# ItsyBitsy_Qwiic.net
KiCad netlist of a schematic drawn in EAGLE
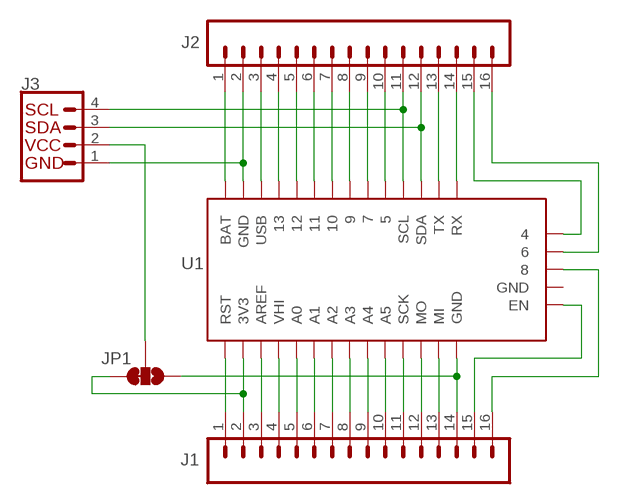
[diagram p0: schematic, sheet 1]

(export (version "E")
  (design (tool "Eeschema 10.0.6"))
  (components
    (comp (ref "J1")
      (value "CONN_161X16_NO_SILK")
      (footprint "eagle-import:1X16_NO_SILK")
      (libsource (lib "eagle-import") (part "CONN_161X16_NO_SILK"))
    )
    (comp (ref "J2")
      (value "CONN_161X16_NO_SILK")
      (footprint "eagle-import:1X16_NO_SILK")
      (libsource (lib "eagle-import") (part "CONN_161X16_NO_SILK"))
    )
    (comp (ref "J3")
      (value "QWIIC_CONNECTORJS-1MM")
      (footprint "eagle-import:1X04_1MM_RA")
      (libsource (lib "eagle-import") (part "QWIIC_CONNECTORJS-1MM"))
    )
    (comp (ref "JP1")
      (value "JUMPER-SMT_3_1-NC_TRACE_SILK")
      (footprint "eagle-import:SMT-JUMPER_3_1-NC_TRACE_SILK")
      (libsource (lib "eagle-import") (part "JUMPER-SMT_3_1-NC_TRACE_SILK"))
    )
    (comp (ref "U1")
      (value "ITSYBITSY-32U4-3V")
      (footprint "eagle-import:ITSYBITYS-32U4")
      (libsource (lib "eagle-import") (part "ITSYBITSY-32U4-3V"))
    )
  )
  (nets
    (net (code "1") (name "/GND") (class "Default")
      (node (ref "U1") (pin "P$16") (pinfunction "GND_P$16") (pintype "power_in"))
    )
    (net (code "2") (name "Net-(J1-Pad14)") (class "Default")
      (node (ref "J1") (pin "14") (pinfunction "14_14") (pintype "passive"))
      (node (ref "JP1") (pin "1") (pinfunction "1_1") (pintype "passive"))
      (node (ref "U1") (pin "P$14") (pinfunction "GND_P$14") (pintype "power_in"))
    )
    (net (code "3") (name "Net-(J3-GND)") (class "Default")
      (node (ref "J2") (pin "2") (pinfunction "2_2") (pintype "passive"))
      (node (ref "J3") (pin "1") (pinfunction "GND_1") (pintype "power_in"))
      (node (ref "U1") (pin "P$32") (pinfunction "GND_P$32") (pintype "power_in"))
    )
    (net (code "4") (name "Net-(J3-SCL)") (class "Default")
      (node (ref "J2") (pin "11") (pinfunction "11_11") (pintype "passive"))
      (node (ref "J3") (pin "4") (pinfunction "SCL_4") (pintype "passive"))
      (node (ref "U1") (pin "P$23") (pinfunction "SCL_P$23") (pintype "bidirectional"))
    )
    (net (code "5") (name "Net-(J3-SDA)") (class "Default")
      (node (ref "J2") (pin "12") (pinfunction "12_12") (pintype "passive"))
      (node (ref "J3") (pin "3") (pinfunction "SDA_3") (pintype "passive"))
      (node (ref "U1") (pin "P$22") (pinfunction "SDA_P$22") (pintype "bidirectional"))
    )
    (net (code "6") (name "Net-(J3-VCC)") (class "Default")
      (node (ref "J3") (pin "2") (pinfunction "VCC_2") (pintype "power_in"))
      (node (ref "JP1") (pin "2") (pinfunction "2_2") (pintype "passive"))
    )
    (net (code "7") (name "Net-(U1-3V3)") (class "Default")
      (node (ref "J1") (pin "2") (pinfunction "2_2") (pintype "passive"))
      (node (ref "JP1") (pin "3") (pinfunction "3_3") (pintype "passive"))
      (node (ref "U1") (pin "P$2") (pinfunction "3V3_P$2") (pintype "power_in"))
    )
    (net (code "8") (name "Net-(U1-4)") (class "Default")
      (node (ref "J2") (pin "15") (pinfunction "15_15") (pintype "passive"))
      (node (ref "U1") (pin "P$19") (pinfunction "4_P$19") (pintype "bidirectional"))
    )
    (net (code "9") (name "Net-(U1-5)") (class "Default")
      (node (ref "J2") (pin "10") (pinfunction "10_10") (pintype "passive"))
      (node (ref "U1") (pin "P$24") (pinfunction "5_P$24") (pintype "bidirectional"))
    )
    (net (code "10") (name "Net-(U1-6)") (class "Default")
      (node (ref "J2") (pin "16") (pinfunction "16_16") (pintype "passive"))
      (node (ref "U1") (pin "P$18") (pinfunction "6_P$18") (pintype "bidirectional"))
    )
    (net (code "11") (name "Net-(U1-7)") (class "Default")
      (node (ref "J2") (pin "9") (pinfunction "9_9") (pintype "passive"))
      (node (ref "U1") (pin "P$25") (pinfunction "7_P$25") (pintype "bidirectional"))
    )
    (net (code "12") (name "Net-(U1-8)") (class "Default")
      (node (ref "J1") (pin "16") (pinfunction "16_16") (pintype "passive"))
      (node (ref "U1") (pin "P$17") (pinfunction "8_P$17") (pintype "bidirectional"))
    )
    (net (code "13") (name "Net-(U1-9)") (class "Default")
      (node (ref "J2") (pin "8") (pinfunction "8_8") (pintype "passive"))
      (node (ref "U1") (pin "P$26") (pinfunction "9_P$26") (pintype "bidirectional"))
    )
    (net (code "14") (name "Net-(U1-10)") (class "Default")
      (node (ref "J2") (pin "7") (pinfunction "7_7") (pintype "passive"))
      (node (ref "U1") (pin "P$27") (pinfunction "10_P$27") (pintype "bidirectional"))
    )
    (net (code "15") (name "Net-(U1-11)") (class "Default")
      (node (ref "J2") (pin "6") (pinfunction "6_6") (pintype "passive"))
      (node (ref "U1") (pin "P$28") (pinfunction "11_P$28") (pintype "bidirectional"))
    )
    (net (code "16") (name "Net-(U1-12)") (class "Default")
      (node (ref "J2") (pin "5") (pinfunction "5_5") (pintype "passive"))
      (node (ref "U1") (pin "P$29") (pinfunction "12_P$29") (pintype "bidirectional"))
    )
    (net (code "17") (name "Net-(U1-13)") (class "Default")
      (node (ref "J2") (pin "4") (pinfunction "4_4") (pintype "passive"))
      (node (ref "U1") (pin "P$30") (pinfunction "13_P$30") (pintype "bidirectional"))
    )
    (net (code "18") (name "Net-(U1-A0)") (class "Default")
      (node (ref "J1") (pin "5") (pinfunction "5_5") (pintype "passive"))
      (node (ref "U1") (pin "P$5") (pinfunction "A0_P$5") (pintype "bidirectional"))
    )
    (net (code "19") (name "Net-(U1-A1)") (class "Default")
      (node (ref "J1") (pin "6") (pinfunction "6_6") (pintype "passive"))
      (node (ref "U1") (pin "P$6") (pinfunction "A1_P$6") (pintype "bidirectional"))
    )
    (net (code "20") (name "Net-(U1-A2)") (class "Default")
      (node (ref "J1") (pin "7") (pinfunction "7_7") (pintype "passive"))
      (node (ref "U1") (pin "P$7") (pinfunction "A2_P$7") (pintype "bidirectional"))
    )
    (net (code "21") (name "Net-(U1-A3)") (class "Default")
      (node (ref "J1") (pin "8") (pinfunction "8_8") (pintype "passive"))
      (node (ref "U1") (pin "P$8") (pinfunction "A3_P$8") (pintype "bidirectional"))
    )
    (net (code "22") (name "Net-(U1-A4)") (class "Default")
      (node (ref "J1") (pin "9") (pinfunction "9_9") (pintype "passive"))
      (node (ref "U1") (pin "P$9") (pinfunction "A4_P$9") (pintype "bidirectional"))
    )
    (net (code "23") (name "Net-(U1-A5)") (class "Default")
      (node (ref "J1") (pin "10") (pinfunction "10_10") (pintype "passive"))
      (node (ref "U1") (pin "P$10") (pinfunction "A5_P$10") (pintype "bidirectional"))
    )
    (net (code "24") (name "Net-(U1-AREF)") (class "Default")
      (node (ref "J1") (pin "3") (pinfunction "3_3") (pintype "passive"))
      (node (ref "U1") (pin "P$3") (pinfunction "AREF_P$3") (pintype "input"))
    )
    (net (code "25") (name "Net-(U1-BAT)") (class "Default")
      (node (ref "J2") (pin "1") (pinfunction "1_1") (pintype "passive"))
      (node (ref "U1") (pin "P$33") (pinfunction "BAT_P$33") (pintype "power_in"))
    )
    (net (code "26") (name "Net-(U1-EN)") (class "Default")
      (node (ref "J1") (pin "15") (pinfunction "15_15") (pintype "passive"))
      (node (ref "U1") (pin "P$15") (pinfunction "EN_P$15") (pintype "input"))
    )
    (net (code "27") (name "Net-(U1-MI)") (class "Default")
      (node (ref "J1") (pin "13") (pinfunction "13_13") (pintype "passive"))
      (node (ref "U1") (pin "P$13") (pinfunction "MI_P$13") (pintype "bidirectional"))
    )
    (net (code "28") (name "Net-(U1-MO)") (class "Default")
      (node (ref "J1") (pin "12") (pinfunction "12_12") (pintype "passive"))
      (node (ref "U1") (pin "P$12") (pinfunction "MO_P$12") (pintype "bidirectional"))
    )
    (net (code "29") (name "Net-(U1-RST)") (class "Default")
      (node (ref "J1") (pin "1") (pinfunction "1_1") (pintype "passive"))
      (node (ref "U1") (pin "P$1") (pinfunction "RST_P$1") (pintype "bidirectional"))
    )
    (net (code "30") (name "Net-(U1-RX)") (class "Default")
      (node (ref "J2") (pin "14") (pinfunction "14_14") (pintype "passive"))
      (node (ref "U1") (pin "P$20") (pinfunction "RX_P$20") (pintype "bidirectional"))
    )
    (net (code "31") (name "Net-(U1-SCK)") (class "Default")
      (node (ref "J1") (pin "11") (pinfunction "11_11") (pintype "passive"))
      (node (ref "U1") (pin "P$11") (pinfunction "SCK_P$11") (pintype "bidirectional"))
    )
    (net (code "32") (name "Net-(U1-TX)") (class "Default")
      (node (ref "J2") (pin "13") (pinfunction "13_13") (pintype "passive"))
      (node (ref "U1") (pin "P$21") (pinfunction "TX_P$21") (pintype "bidirectional"))
    )
    (net (code "33") (name "Net-(U1-USB)") (class "Default")
      (node (ref "J2") (pin "3") (pinfunction "3_3") (pintype "passive"))
      (node (ref "U1") (pin "P$31") (pinfunction "USB_P$31") (pintype "power_in"))
    )
    (net (code "34") (name "Net-(U1-VHI)") (class "Default")
      (node (ref "J1") (pin "4") (pinfunction "4_4") (pintype "passive"))
      (node (ref "U1") (pin "P$4") (pinfunction "VHI_P$4") (pintype "power_in"))
    )
  )
)
